# AT86RF231.net
KiCad netlist of a schematic drawn in Altium Designer
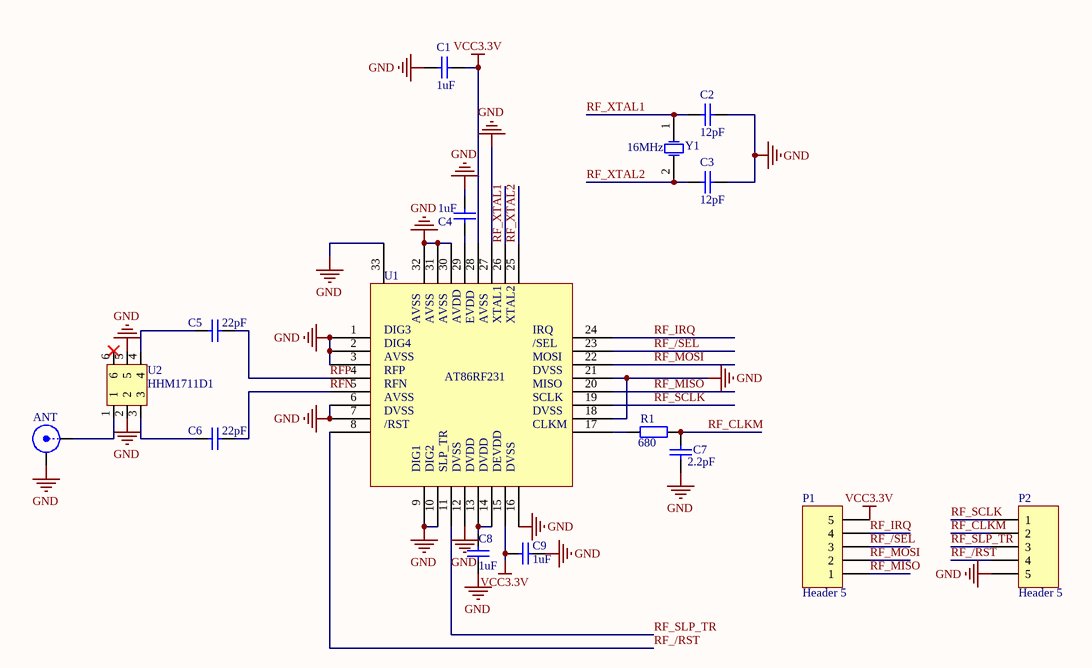
[diagram p0: AT86RF231.SchDoc]

(export (version "E")
  (design (tool "Eeschema 10.0.6"))
  (components
    (comp (ref "ANT")
      (value "SMA")
      (footprint "ANT")
      (description "SMB Straight Connector")
      (fields (field (name "PUBLISHER") "Altium Limited"))
      (libsource (lib "Miscellaneous Connectors") (part "SMB"))
    )
    (comp (ref "C1")
      (value "1uF")
      (footprint "0402")
      (description "Capacitor")
      (fields (field (name "PUBLISHER") "Altium Limited"))
      (libsource (lib "Miscellaneous Devices") (part "Cap"))
    )
    (comp (ref "C2")
      (value "12pF")
      (footprint "0402")
      (description "Capacitor")
      (fields (field (name "PUBLISHER") "Altium Limited"))
      (libsource (lib "Miscellaneous Devices") (part "Cap"))
    )
    (comp (ref "C3")
      (value "12pF")
      (footprint "0402")
      (description "Capacitor")
      (fields (field (name "PUBLISHER") "Altium Limited"))
      (libsource (lib "Miscellaneous Devices") (part "Cap"))
    )
    (comp (ref "C4")
      (value "1uF")
      (footprint "0402")
      (description "Capacitor")
      (fields (field (name "PUBLISHER") "Altium Limited"))
      (libsource (lib "Miscellaneous Devices") (part "Cap"))
    )
    (comp (ref "C5")
      (value "22pF")
      (footprint "0402")
      (description "Capacitor")
      (fields (field (name "PUBLISHER") "Altium Limited"))
      (libsource (lib "Miscellaneous Devices") (part "Cap"))
    )
    (comp (ref "C6")
      (value "22pF")
      (footprint "0402")
      (description "Capacitor")
      (fields (field (name "PUBLISHER") "Altium Limited"))
      (libsource (lib "Miscellaneous Devices") (part "Cap"))
    )
    (comp (ref "C7")
      (value "2.2pF")
      (footprint "0402")
      (description "Capacitor")
      (fields (field (name "PUBLISHER") "Altium Limited"))
      (libsource (lib "Miscellaneous Devices") (part "Cap"))
    )
    (comp (ref "C8")
      (value "1uF")
      (footprint "0402")
      (description "Capacitor")
      (fields (field (name "PUBLISHER") "Altium Limited"))
      (libsource (lib "Miscellaneous Devices") (part "Cap"))
    )
    (comp (ref "C9")
      (value "1uF")
      (footprint "0402")
      (description "Capacitor")
      (fields (field (name "PUBLISHER") "Altium Limited"))
      (libsource (lib "Miscellaneous Devices") (part "Cap"))
    )
    (comp (ref "P1")
      (value "Header 5")
      (footprint "HDR1X5")
      (description "Header, 5-Pin")
      (fields (field (name "PUBLISHER") "Altium Limited"))
      (libsource (lib "Miscellaneous Connectors") (part "Header 5"))
    )
    (comp (ref "P2")
      (value "Header 5")
      (footprint "HDR1X5")
      (description "Header, 5-Pin")
      (fields (field (name "PUBLISHER") "Altium Limited"))
      (libsource (lib "") (part "Header 5_1"))
    )
    (comp (ref "R1")
      (value "680")
      (footprint "0402")
      (description "Resistor")
      (fields (field (name "PUBLISHER") "Altium Limited"))
      (libsource (lib "Miscellaneous Devices") (part "Res2"))
    )
    (comp (ref "U1")
      (value "AT86RF231")
      (footprint "AT86")
      (libsource (lib "OpenMoteSTM") (part "AT86RF231"))
    )
    (comp (ref "U2")
      (value "HHM1711D1")
      (footprint "HHM1711D1")
      (description "HHM1711D1 For Bluetooth & IEEE802.11b/g")
      (libsource (lib "OpenMoteSTM") (part "HHM1711D1"))
    )
    (comp (ref "Y1")
      (value "16MHz")
      (footprint "XTAL_5032_SMD")
      (description "Crystal Oscillator")
      (fields (field (name "Comment") "XTAL") (field (name "PUBLISHER") "Altium Limited"))
      (libsource (lib "Miscellaneous Devices") (part "XTAL"))
    )
  )
  (nets
    (net (code "1") (name "/RFN") (class "Default")
      (node (ref "C6") (pin "2") (pinfunction "2_2") (pintype "passive"))
      (node (ref "U1") (pin "5") (pinfunction "5_5") (pintype "passive"))
    )
    (net (code "2") (name "/RFP") (class "Default")
      (node (ref "C5") (pin "2") (pinfunction "2_2") (pintype "passive"))
      (node (ref "U1") (pin "4") (pinfunction "4_4") (pintype "passive"))
    )
    (net (code "3") (name "/RF_CLKM") (class "Default")
      (node (ref "C7") (pin "2") (pinfunction "2_2") (pintype "passive"))
      (node (ref "P2") (pin "2") (pinfunction "2_2") (pintype "passive"))
      (node (ref "R1") (pin "2") (pinfunction "2_2") (pintype "passive"))
    )
    (net (code "4") (name "/RF_IRQ") (class "Default")
      (node (ref "P1") (pin "4") (pinfunction "4_4") (pintype "passive"))
      (node (ref "U1") (pin "24") (pinfunction "24_24") (pintype "passive"))
    )
    (net (code "5") (name "/RF_MISO") (class "Default")
      (node (ref "P1") (pin "1") (pinfunction "1_1") (pintype "passive"))
      (node (ref "U1") (pin "20") (pinfunction "20_20") (pintype "passive"))
    )
    (net (code "6") (name "/RF_MOSI") (class "Default")
      (node (ref "P1") (pin "2") (pinfunction "2_2") (pintype "passive"))
      (node (ref "U1") (pin "22") (pinfunction "22_22") (pintype "passive"))
    )
    (net (code "7") (name "/RF_SCLK") (class "Default")
      (node (ref "P2") (pin "1") (pinfunction "1_1") (pintype "passive"))
      (node (ref "U1") (pin "19") (pinfunction "19_19") (pintype "passive"))
    )
    (net (code "8") (name "/RF_SLP_TR") (class "Default")
      (node (ref "P2") (pin "3") (pinfunction "3_3") (pintype "passive"))
      (node (ref "U1") (pin "11") (pinfunction "11_11") (pintype "passive"))
    )
    (net (code "9") (name "/RF_XTAL1") (class "Default")
      (node (ref "C2") (pin "2") (pinfunction "2_2") (pintype "passive"))
      (node (ref "U1") (pin "26") (pinfunction "26_26") (pintype "passive"))
      (node (ref "Y1") (pin "1") (pinfunction "OSC1_1") (pintype "passive"))
    )
    (net (code "10") (name "/RF_XTAL2") (class "Default")
      (node (ref "C3") (pin "2") (pinfunction "2_2") (pintype "passive"))
      (node (ref "U1") (pin "25") (pinfunction "25_25") (pintype "passive"))
      (node (ref "Y1") (pin "2") (pinfunction "OSC2_2") (pintype "passive"))
    )
    (net (code "11") (name "/RF_{slash}RST") (class "Default")
      (node (ref "P2") (pin "4") (pinfunction "4_4") (pintype "passive"))
      (node (ref "U1") (pin "8") (pinfunction "8_8") (pintype "passive"))
    )
    (net (code "12") (name "/RF_{slash}SEL") (class "Default")
      (node (ref "P1") (pin "3") (pinfunction "3_3") (pintype "passive"))
      (node (ref "U1") (pin "23") (pinfunction "23_23") (pintype "passive"))
    )
    (net (code "13") (name "GND") (class "Default")
      (node (ref "ANT") (pin "2") (pinfunction "Y_2") (pintype "passive"))
      (node (ref "C1") (pin "1") (pinfunction "1_1") (pintype "passive"))
      (node (ref "C2") (pin "1") (pinfunction "1_1") (pintype "passive"))
      (node (ref "C3") (pin "1") (pinfunction "1_1") (pintype "passive"))
      (node (ref "C4") (pin "1") (pinfunction "1_1") (pintype "passive"))
      (node (ref "C7") (pin "1") (pinfunction "1_1") (pintype "passive"))
      (node (ref "C8") (pin "1") (pinfunction "1_1") (pintype "passive"))
      (node (ref "C9") (pin "1") (pinfunction "1_1") (pintype "passive"))
      (node (ref "P2") (pin "5") (pinfunction "5_5") (pintype "passive"))
      (node (ref "U1") (pin "1") (pinfunction "1_1") (pintype "passive"))
      (node (ref "U1") (pin "10") (pinfunction "10_10") (pintype "passive"))
      (node (ref "U1") (pin "12") (pinfunction "12_12") (pintype "passive"))
      (node (ref "U1") (pin "16") (pinfunction "16_16") (pintype "passive"))
      (node (ref "U1") (pin "18") (pinfunction "18_18") (pintype "passive"))
      (node (ref "U1") (pin "2") (pinfunction "2_2") (pintype "passive"))
      (node (ref "U1") (pin "21") (pinfunction "21_21") (pintype "passive"))
      (node (ref "U1") (pin "27") (pinfunction "27_27") (pintype "passive"))
      (node (ref "U1") (pin "3") (pinfunction "3_3") (pintype "passive"))
      (node (ref "U1") (pin "30") (pinfunction "30_30") (pintype "passive"))
      (node (ref "U1") (pin "31") (pinfunction "31_31") (pintype "passive"))
      (node (ref "U1") (pin "32") (pinfunction "32_32") (pintype "passive"))
      (node (ref "U1") (pin "33") (pinfunction "33_33") (pintype "passive"))
      (node (ref "U1") (pin "6") (pinfunction "6_6") (pintype "passive"))
      (node (ref "U1") (pin "7") (pinfunction "7_7") (pintype "passive"))
      (node (ref "U1") (pin "9") (pinfunction "9_9") (pintype "passive"))
      (node (ref "U2") (pin "2") (pinfunction "2_2") (pintype "passive"))
      (node (ref "U2") (pin "5") (pinfunction "5_5") (pintype "passive"))
    )
    (net (code "14") (name "Net-(ANT-X)") (class "Default")
      (node (ref "ANT") (pin "1") (pinfunction "X_1") (pintype "passive"))
      (node (ref "U2") (pin "1") (pinfunction "1_1") (pintype "passive"))
    )
    (net (code "15") (name "Net-(C4-Pad2)") (class "Default")
      (node (ref "C4") (pin "2") (pinfunction "2_2") (pintype "passive"))
      (node (ref "U1") (pin "29") (pinfunction "29_29") (pintype "passive"))
    )
    (net (code "16") (name "Net-(C5-Pad1)") (class "Default")
      (node (ref "C5") (pin "1") (pinfunction "1_1") (pintype "passive"))
      (node (ref "U2") (pin "4") (pinfunction "4_4") (pintype "passive"))
    )
    (net (code "17") (name "Net-(C6-Pad1)") (class "Default")
      (node (ref "C6") (pin "1") (pinfunction "1_1") (pintype "passive"))
      (node (ref "U2") (pin "3") (pinfunction "3_3") (pintype "passive"))
    )
    (net (code "18") (name "Net-(C8-Pad2)") (class "Default")
      (node (ref "C8") (pin "2") (pinfunction "2_2") (pintype "passive"))
      (node (ref "U1") (pin "13") (pinfunction "13_13") (pintype "passive"))
      (node (ref "U1") (pin "14") (pinfunction "14_14") (pintype "passive"))
    )
    (net (code "19") (name "Net-(R1-Pad1)") (class "Default")
      (node (ref "R1") (pin "1") (pinfunction "1_1") (pintype "passive"))
      (node (ref "U1") (pin "17") (pinfunction "17_17") (pintype "passive"))
    )
    (net (code "20") (name "VCC3.3V") (class "Default")
      (node (ref "C1") (pin "2") (pinfunction "2_2") (pintype "passive"))
      (node (ref "C9") (pin "2") (pinfunction "2_2") (pintype "passive"))
      (node (ref "P1") (pin "5") (pinfunction "5_5") (pintype "passive"))
      (node (ref "U1") (pin "15") (pinfunction "15_15") (pintype "passive"))
      (node (ref "U1") (pin "28") (pinfunction "28_28") (pintype "passive"))
    )
    (net (code "21") (name "unconnected-(U2-Pad6)") (class "Default")
      (node (ref "U2") (pin "6") (pinfunction "6_6") (pintype "passive+no_connect"))
    )
  )
)
